# Camera_Shield_Camera_Interface.net
KiCad netlist of a schematic drawn in Altium Designer
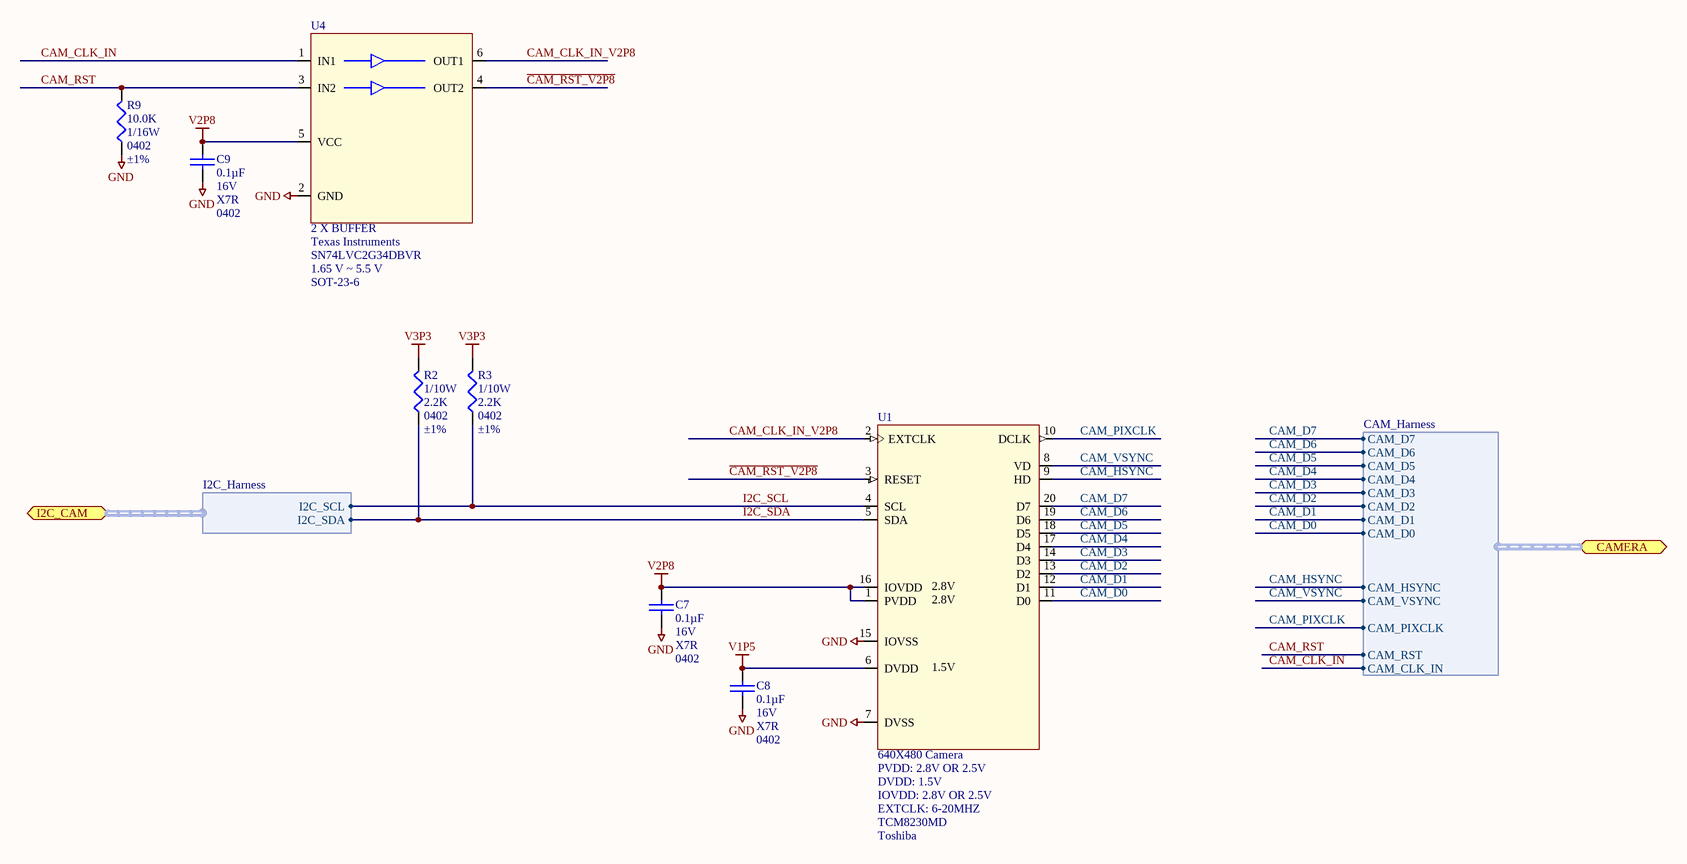
[diagram p0: Camera_Shield_Camera_Interface.SchDoc]

(export (version "E")
  (design (tool "Eeschema 10.0.6"))
  (components
    (comp (ref "C7")
      (value "0.1uF")
      (footprint "C_0402")
      (description "CAP CER .10UF 16V X7R 0402")
      (fields
        (field (name "MANUFACTURER") "TDK Corporation")
        (field (name "MANUFACTURER PART NUMBER") "C1005X7R1C104K")
        (field (name "CAPACITANCE") "0.1µF")
        (field (name "VOLTAGE - RATED") "16V")
        (field (name "TEMPERATURE COEFFICIENT") "X7R")
        (field (name "PACKAGE / CASE") "0402")
      )
      (libsource (lib "Main Library") (part "C_0402_0.1UF_16V"))
    )
    (comp (ref "C8")
      (value "0.1uF")
      (footprint "C_0402")
      (description "CAP CER .10UF 16V X7R 0402")
      (fields
        (field (name "MANUFACTURER") "TDK Corporation")
        (field (name "MANUFACTURER PART NUMBER") "C1005X7R1C104K")
        (field (name "CAPACITANCE") "0.1µF")
        (field (name "VOLTAGE - RATED") "16V")
        (field (name "TEMPERATURE COEFFICIENT") "X7R")
        (field (name "PACKAGE / CASE") "0402")
      )
      (libsource (lib "Main Library") (part "C_0402_0.1UF_16V"))
    )
    (comp (ref "C9")
      (value "0.1uF")
      (footprint "C_0402")
      (description "CAP CER .10UF 16V X7R 0402")
      (fields
        (field (name "MANUFACTURER") "TDK Corporation")
        (field (name "MANUFACTURER PART NUMBER") "C1005X7R1C104K")
        (field (name "CAPACITANCE") "0.1µF")
        (field (name "VOLTAGE - RATED") "16V")
        (field (name "TEMPERATURE COEFFICIENT") "X7R")
        (field (name "PACKAGE / CASE") "0402")
      )
      (libsource (lib "Main Library") (part "C_0402_0.1UF_16V"))
    )
    (comp (ref "R2")
      (value "2.2k Ohms")
      (footprint "ERA-0402")
      (description "RES 2.20K OHM 1/10W 1% 0402 SMD")
      (fields
        (field (name "MANUFACTURER") "Yageo")
        (field (name "MANUFACTURER PART NUMBER") "RC0402FR-072K2L")
        (field (name "POWER (WATTS)") "1/10W")
        (field (name "RESISTANCE IN OHMS") "2.2K")
        (field (name "CASE") "0402")
        (field (name "TOLERANCE") "±1%")
      )
      (libsource (lib "Main LibraryX") (part "R_0402_2.2K"))
    )
    (comp (ref "R3")
      (value "2.2k Ohms")
      (footprint "ERA-0402")
      (description "RES 2.20K OHM 1/10W 1% 0402 SMD")
      (fields
        (field (name "MANUFACTURER") "Yageo")
        (field (name "MANUFACTURER PART NUMBER") "RC0402FR-072K2L")
        (field (name "POWER (WATTS)") "1/10W")
        (field (name "RESISTANCE IN OHMS") "2.2K")
        (field (name "CASE") "0402")
        (field (name "TOLERANCE") "±1%")
      )
      (libsource (lib "Main LibraryX") (part "R_0402_2.2K"))
    )
    (comp (ref "R9")
      (value "R_0402_10.0K")
      (footprint "R_0402")
      (description "RES 10.0K OHM 1/16W 1% 0402 SMD")
      (fields
        (field (name "MANUFACTURER") "Stackpole Electronics Inc")
        (field (name "MANUFACTURER PART NUMBER") "RMCF0402FT10K0")
        (field (name "RESISTANCE IN OHMS") "10.0K")
        (field (name "POWER (WATTS)") "1/16W")
        (field (name "CASE") "0402")
        (field (name "TOLERANCE") "±1%")
      )
      (libsource (lib "Main Library") (part "R_0402_10.0K"))
    )
    (comp (ref "U1")
      (value "640X480 Camera")
      (footprint "TCM8230MD")
      (description "640 x 480 SPARKFUN CAMERA")
      (fields
        (field (name "PVDD") "2.8V OR 2.5V")
        (field (name "DVDD") "1.5V")
        (field (name "IOVDD") "2.8V OR 2.5V")
        (field (name "EXTCLK") "6-20MHZ")
        (field (name "MANUFACTURER PART NUMBER") "TCM8230MD")
        (field (name "MANUFACTURER") "Toshiba")
      )
      (libsource (lib "Main LibraryX") (part "U_TCM8230MD_CAMERA"))
    )
    (comp (ref "U4")
      (value "2 X BUFFER")
      (footprint "SOT23-6")
      (description "IC BUFFER DUAL NON-INV SOT23-6")
      (fields
        (field (name "MANUFACTURER") "Texas Instruments")
        (field (name "MANUFACTURER PART NUMBER") "SN74LVC2G34DBVR")
        (field (name "VOLTAGE - SUPPLY") "1.65 V ~ 5.5 V")
        (field (name "SUPPLIER DEVICE PACKAGE") "SOT-23-6")
      )
      (libsource (lib "Main Library") (part "U_SN74LVC2G34DBVR"))
    )
  )
  (nets
    (net (code "3") (name "/CAM_CLK_IN") (class "Default")
      (node (ref "U4") (pin "1") (pinfunction "IN1_1") (pintype "passive"))
    )
    (net (code "4") (name "/CAM_CLK_IN_V2P8") (class "Default")
      (node (ref "U1") (pin "2") (pinfunction "EXTCLK_2") (pintype "input"))
      (node (ref "U4") (pin "6") (pinfunction "OUT1_6") (pintype "passive"))
    )
    (net (code "5") (name "/CAM_D0") (class "Default")
      (node (ref "U1") (pin "11") (pinfunction "D0_11") (pintype "passive"))
    )
    (net (code "6") (name "/CAM_D1") (class "Default")
      (node (ref "U1") (pin "12") (pinfunction "D1_12") (pintype "passive"))
    )
    (net (code "7") (name "/CAM_D2") (class "Default")
      (node (ref "U1") (pin "13") (pinfunction "D2_13") (pintype "passive"))
    )
    (net (code "8") (name "/CAM_D3") (class "Default")
      (node (ref "U1") (pin "14") (pinfunction "D3_14") (pintype "passive"))
    )
    (net (code "9") (name "/CAM_D4") (class "Default")
      (node (ref "U1") (pin "17") (pinfunction "D4_17") (pintype "passive"))
    )
    (net (code "10") (name "/CAM_D5") (class "Default")
      (node (ref "U1") (pin "18") (pinfunction "D5_18") (pintype "passive"))
    )
    (net (code "11") (name "/CAM_D6") (class "Default")
      (node (ref "U1") (pin "19") (pinfunction "D6_19") (pintype "passive"))
    )
    (net (code "12") (name "/CAM_D7") (class "Default")
      (node (ref "U1") (pin "20") (pinfunction "D7_20") (pintype "passive"))
    )
    (net (code "13") (name "/CAM_HSYNC") (class "Default")
      (node (ref "U1") (pin "9") (pinfunction "HD_9") (pintype "passive"))
    )
    (net (code "14") (name "/CAM_PIXCLK") (class "Default")
      (node (ref "U1") (pin "10") (pinfunction "DCLK_10") (pintype "output"))
    )
    (net (code "15") (name "/CAM_RST") (class "Default")
      (node (ref "R9") (pin "1") (pinfunction "1_1") (pintype "passive"))
      (node (ref "U4") (pin "3") (pinfunction "IN2_3") (pintype "passive"))
    )
    (net (code "16") (name "/CAM_VSYNC") (class "Default")
      (node (ref "U1") (pin "8") (pinfunction "VD_8") (pintype "passive"))
    )
    (net (code "17") (name "/I2C_SCL") (class "Default")
      (node (ref "R3") (pin "2") (pinfunction "2_2") (pintype "passive"))
      (node (ref "U1") (pin "4") (pinfunction "SCL_4") (pintype "passive"))
    )
    (net (code "18") (name "/I2C_SDA") (class "Default")
      (node (ref "R2") (pin "2") (pinfunction "2_2") (pintype "passive"))
      (node (ref "U1") (pin "5") (pinfunction "SDA_5") (pintype "passive"))
    )
    (net (code "21") (name "/~{CAM_RST_V2P8}") (class "Default")
      (node (ref "U1") (pin "3") (pinfunction "RESET_3") (pintype "input"))
      (node (ref "U4") (pin "4") (pinfunction "OUT2_4") (pintype "passive"))
    )
    (net (code "22") (name "GND") (class "Default")
      (node (ref "C7") (pin "1") (pinfunction "1_1") (pintype "passive"))
      (node (ref "C8") (pin "1") (pinfunction "1_1") (pintype "passive"))
      (node (ref "C9") (pin "1") (pinfunction "1_1") (pintype "passive"))
      (node (ref "R9") (pin "2") (pinfunction "2_2") (pintype "passive"))
      (node (ref "U1") (pin "15") (pinfunction "IOVSS_15") (pintype "passive"))
      (node (ref "U1") (pin "7") (pinfunction "DVSS_7") (pintype "power_in"))
      (node (ref "U4") (pin "2") (pinfunction "GND_2") (pintype "passive"))
    )
    (net (code "23") (name "V1P5") (class "Default")
      (node (ref "C8") (pin "2") (pinfunction "2_2") (pintype "passive"))
      (node (ref "U1") (pin "6") (pinfunction "DVDD_6") (pintype "power_in"))
    )
    (net (code "24") (name "V2P8") (class "Default")
      (node (ref "C7") (pin "2") (pinfunction "2_2") (pintype "passive"))
      (node (ref "C9") (pin "2") (pinfunction "2_2") (pintype "passive"))
      (node (ref "U1") (pin "1") (pinfunction "PVDD_1") (pintype "passive"))
      (node (ref "U1") (pin "16") (pinfunction "IOVDD_16") (pintype "power_in"))
      (node (ref "U4") (pin "5") (pinfunction "VCC_5") (pintype "passive"))
    )
    (net (code "25") (name "V3P3") (class "Default")
      (node (ref "R2") (pin "1") (pinfunction "1_1") (pintype "passive"))
      (node (ref "R3") (pin "1") (pinfunction "1_1") (pintype "passive"))
    )
  )
)
